# LEDs.net
KiCad netlist of a schematic drawn in EAGLE
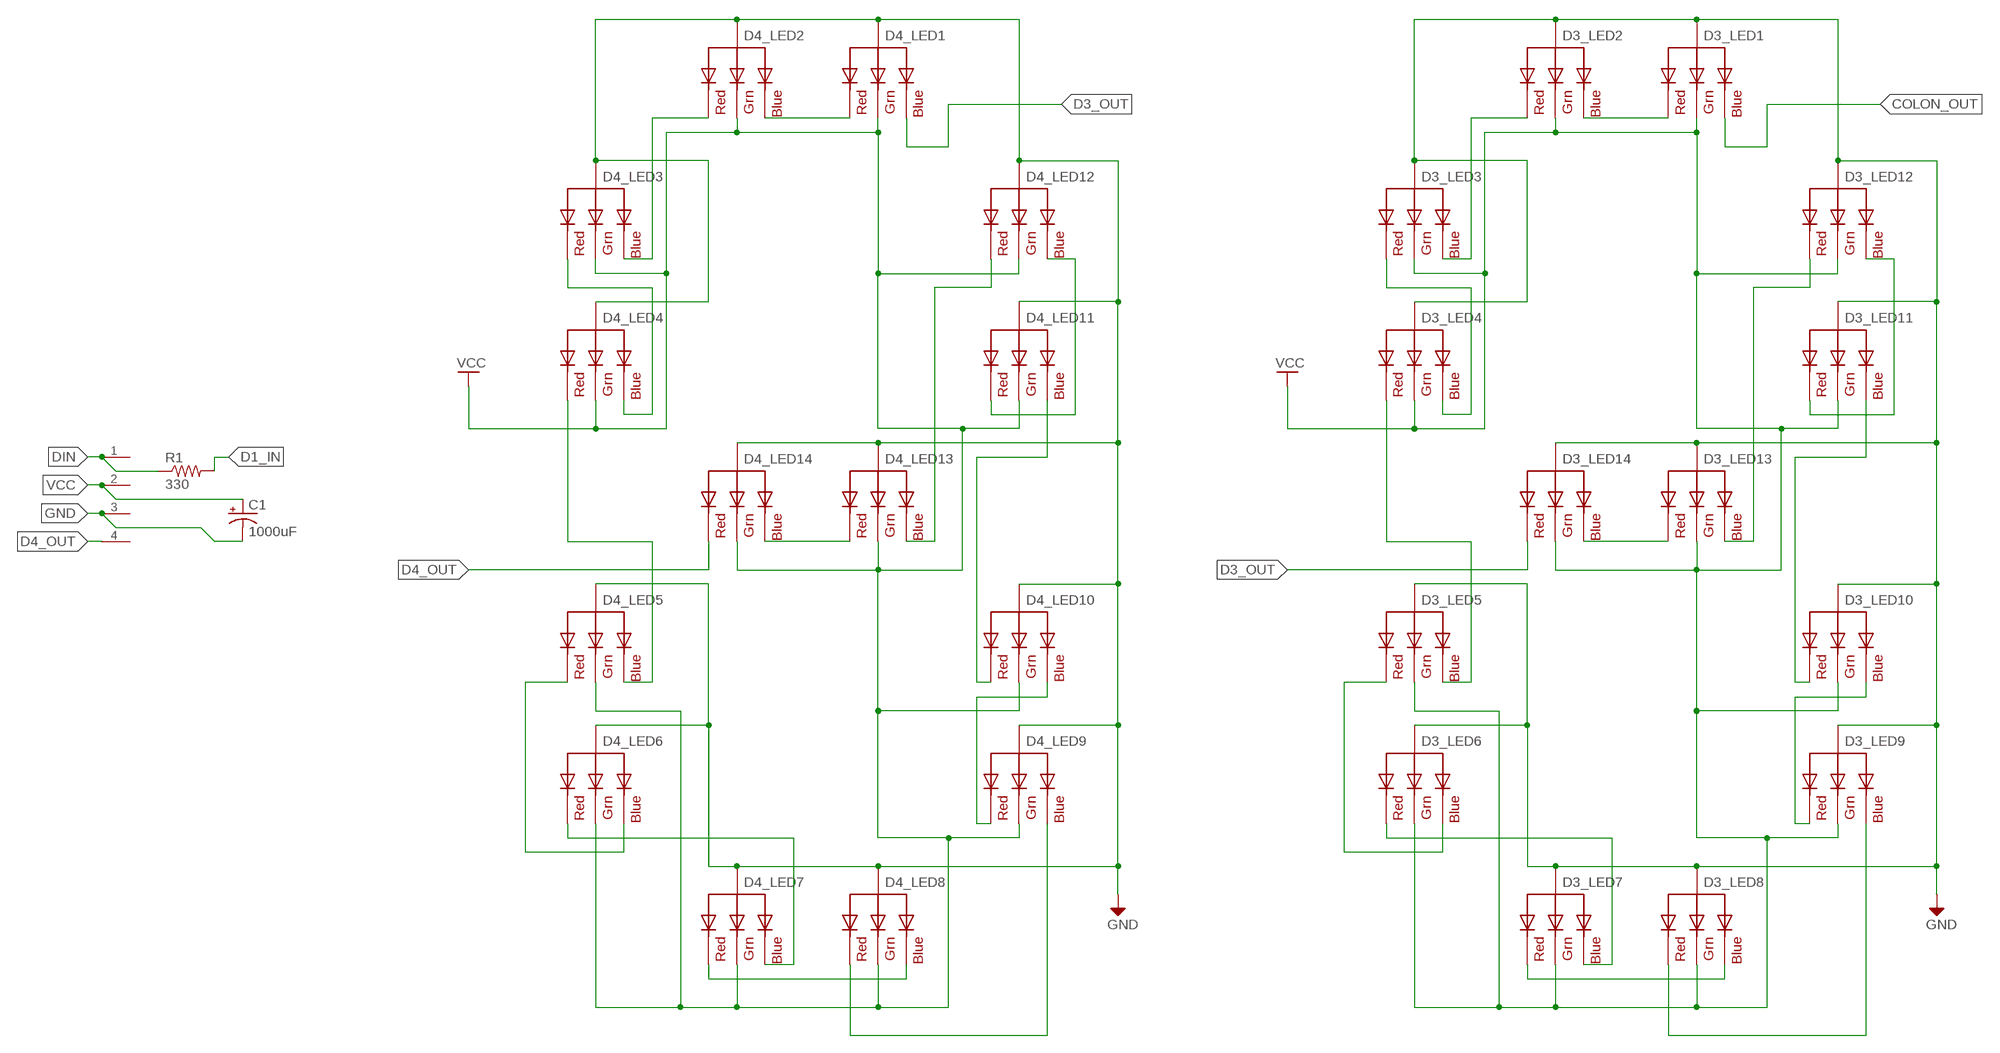
[diagram p0: schematic, sheet 1, part 1 of 2]
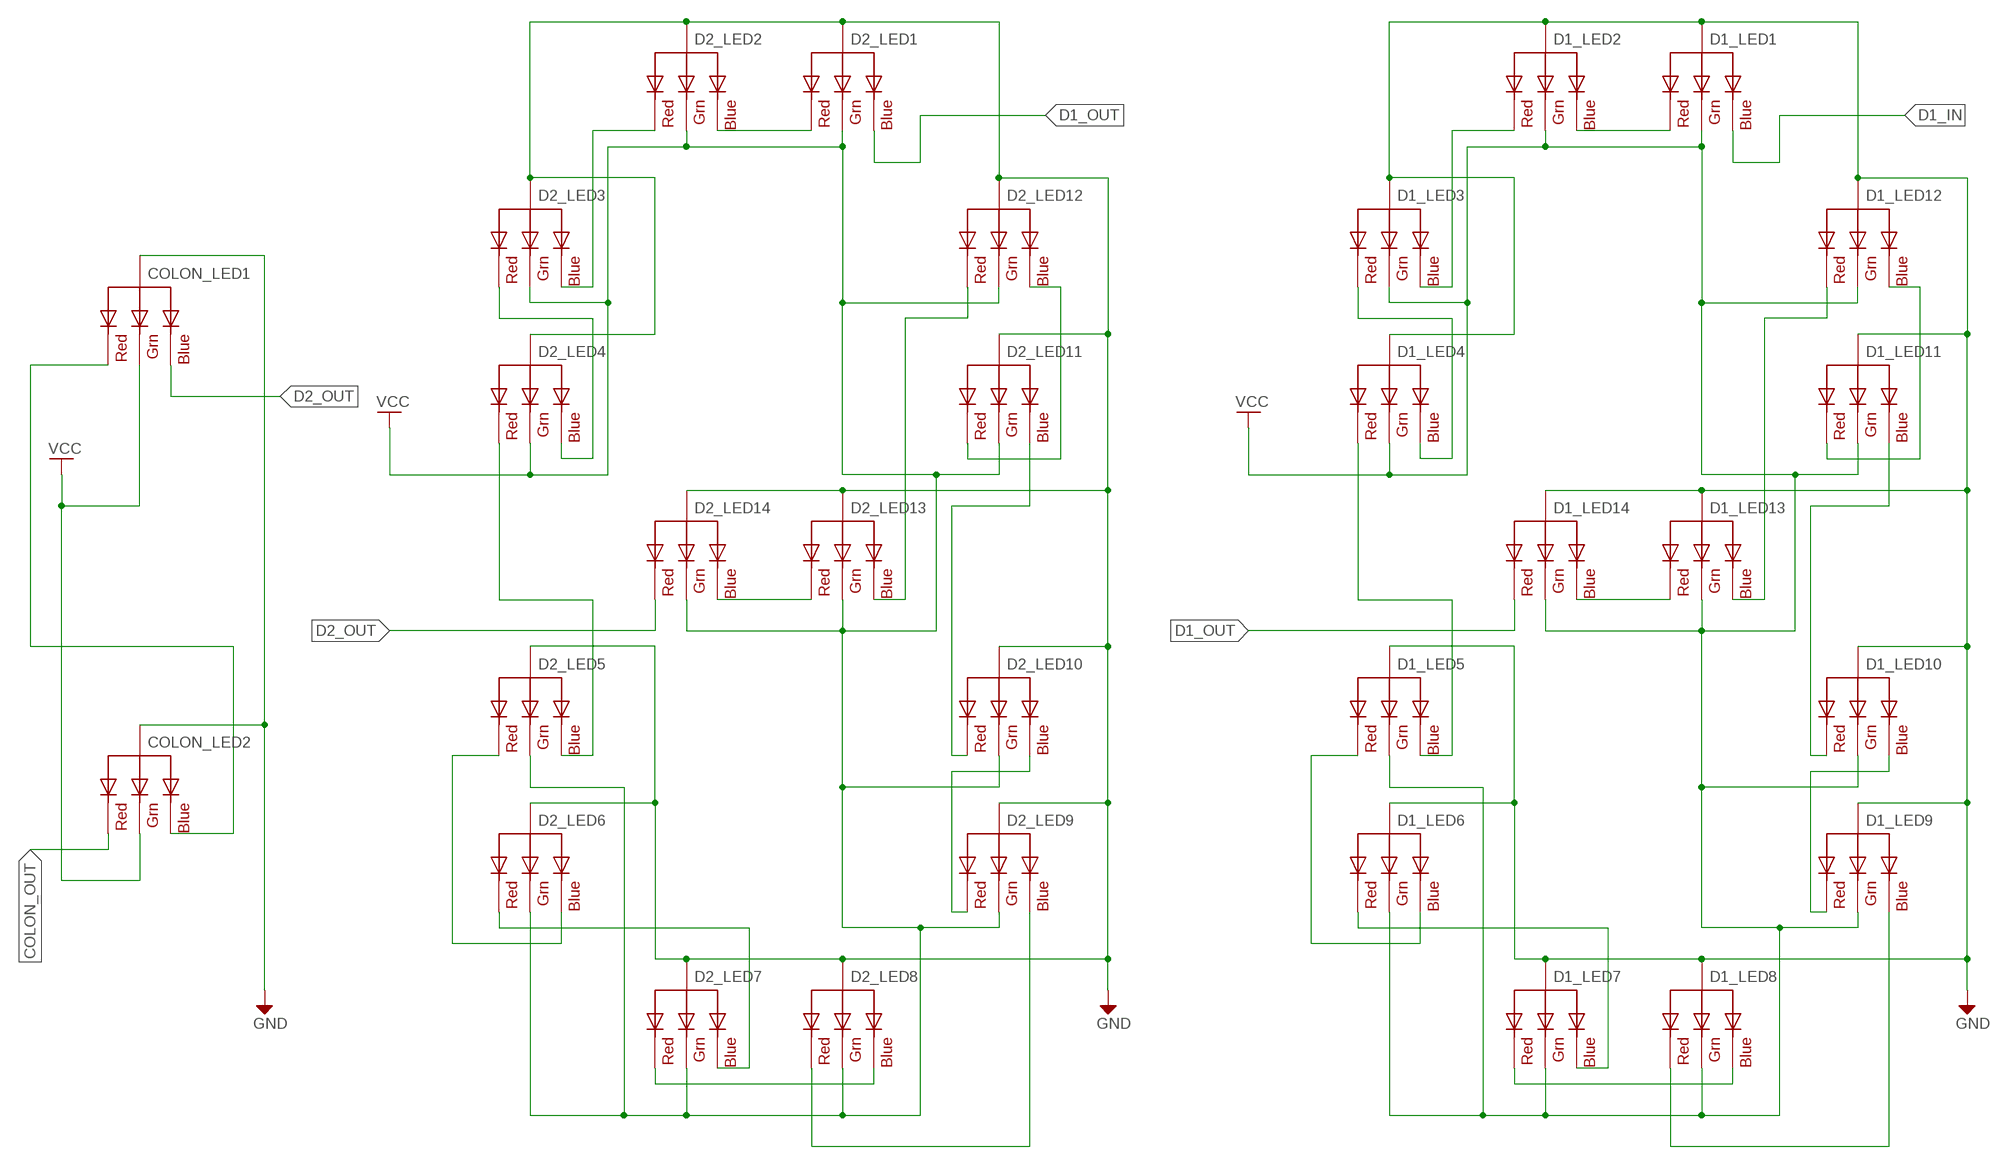
[diagram p1: schematic, sheet 1, part 2 of 2]

(export (version "E")
  (design (tool "Eeschema 10.0.6"))
  (components
    (comp (ref "C1")
      (value "1000uF")
      (footprint "eagle-import:E2,5-6")
      (libsource (lib "eagle-import") (part "CPOL-USE2.5-6"))
    )
    (comp (ref "COLON_LED1")
      (value "RGBLED_CA-5MM")
      (footprint "eagle-import:LED5MMRGB")
      (libsource (lib "eagle-import") (part "RGBLED_CA-5MM"))
    )
    (comp (ref "COLON_LED2")
      (value "RGBLED_CA-5MM")
      (footprint "eagle-import:LED5MMRGB")
      (libsource (lib "eagle-import") (part "RGBLED_CA-5MM"))
    )
    (comp (ref "D1_LED1")
      (value "RGBLED_CA-5MM")
      (footprint "eagle-import:LED5MMRGB")
      (libsource (lib "eagle-import") (part "RGBLED_CA-5MM"))
    )
    (comp (ref "D1_LED2")
      (value "RGBLED_CA-5MM")
      (footprint "eagle-import:LED5MMRGB")
      (libsource (lib "eagle-import") (part "RGBLED_CA-5MM"))
    )
    (comp (ref "D1_LED3")
      (value "RGBLED_CA-5MM")
      (footprint "eagle-import:LED5MMRGB")
      (libsource (lib "eagle-import") (part "RGBLED_CA-5MM"))
    )
    (comp (ref "D1_LED4")
      (value "RGBLED_CA-5MM")
      (footprint "eagle-import:LED5MMRGB")
      (libsource (lib "eagle-import") (part "RGBLED_CA-5MM"))
    )
    (comp (ref "D1_LED5")
      (value "RGBLED_CA-5MM")
      (footprint "eagle-import:LED5MMRGB")
      (libsource (lib "eagle-import") (part "RGBLED_CA-5MM"))
    )
    (comp (ref "D1_LED6")
      (value "RGBLED_CA-5MM")
      (footprint "eagle-import:LED5MMRGB")
      (libsource (lib "eagle-import") (part "RGBLED_CA-5MM"))
    )
    (comp (ref "D1_LED7")
      (value "RGBLED_CA-5MM")
      (footprint "eagle-import:LED5MMRGB")
      (libsource (lib "eagle-import") (part "RGBLED_CA-5MM"))
    )
    (comp (ref "D1_LED8")
      (value "RGBLED_CA-5MM")
      (footprint "eagle-import:LED5MMRGB")
      (libsource (lib "eagle-import") (part "RGBLED_CA-5MM"))
    )
    (comp (ref "D1_LED9")
      (value "RGBLED_CA-5MM")
      (footprint "eagle-import:LED5MMRGB")
      (libsource (lib "eagle-import") (part "RGBLED_CA-5MM"))
    )
    (comp (ref "D1_LED10")
      (value "RGBLED_CA-5MM")
      (footprint "eagle-import:LED5MMRGB")
      (libsource (lib "eagle-import") (part "RGBLED_CA-5MM"))
    )
    (comp (ref "D1_LED11")
      (value "RGBLED_CA-5MM")
      (footprint "eagle-import:LED5MMRGB")
      (libsource (lib "eagle-import") (part "RGBLED_CA-5MM"))
    )
    (comp (ref "D1_LED12")
      (value "RGBLED_CA-5MM")
      (footprint "eagle-import:LED5MMRGB")
      (libsource (lib "eagle-import") (part "RGBLED_CA-5MM"))
    )
    (comp (ref "D1_LED13")
      (value "RGBLED_CA-5MM")
      (footprint "eagle-import:LED5MMRGB")
      (libsource (lib "eagle-import") (part "RGBLED_CA-5MM"))
    )
    (comp (ref "D1_LED14")
      (value "RGBLED_CA-5MM")
      (footprint "eagle-import:LED5MMRGB")
      (libsource (lib "eagle-import") (part "RGBLED_CA-5MM"))
    )
    (comp (ref "D2_LED1")
      (value "RGBLED_CA-5MM")
      (footprint "eagle-import:LED5MMRGB")
      (libsource (lib "eagle-import") (part "RGBLED_CA-5MM"))
    )
    (comp (ref "D2_LED2")
      (value "RGBLED_CA-5MM")
      (footprint "eagle-import:LED5MMRGB")
      (libsource (lib "eagle-import") (part "RGBLED_CA-5MM"))
    )
    (comp (ref "D2_LED3")
      (value "RGBLED_CA-5MM")
      (footprint "eagle-import:LED5MMRGB")
      (libsource (lib "eagle-import") (part "RGBLED_CA-5MM"))
    )
    (comp (ref "D2_LED4")
      (value "RGBLED_CA-5MM")
      (footprint "eagle-import:LED5MMRGB")
      (libsource (lib "eagle-import") (part "RGBLED_CA-5MM"))
    )
    (comp (ref "D2_LED5")
      (value "RGBLED_CA-5MM")
      (footprint "eagle-import:LED5MMRGB")
      (libsource (lib "eagle-import") (part "RGBLED_CA-5MM"))
    )
    (comp (ref "D2_LED6")
      (value "RGBLED_CA-5MM")
      (footprint "eagle-import:LED5MMRGB")
      (libsource (lib "eagle-import") (part "RGBLED_CA-5MM"))
    )
    (comp (ref "D2_LED7")
      (value "RGBLED_CA-5MM")
      (footprint "eagle-import:LED5MMRGB")
      (libsource (lib "eagle-import") (part "RGBLED_CA-5MM"))
    )
    (comp (ref "D2_LED8")
      (value "RGBLED_CA-5MM")
      (footprint "eagle-import:LED5MMRGB")
      (libsource (lib "eagle-import") (part "RGBLED_CA-5MM"))
    )
    (comp (ref "D2_LED9")
      (value "RGBLED_CA-5MM")
      (footprint "eagle-import:LED5MMRGB")
      (libsource (lib "eagle-import") (part "RGBLED_CA-5MM"))
    )
    (comp (ref "D2_LED10")
      (value "RGBLED_CA-5MM")
      (footprint "eagle-import:LED5MMRGB")
      (libsource (lib "eagle-import") (part "RGBLED_CA-5MM"))
    )
    (comp (ref "D2_LED11")
      (value "RGBLED_CA-5MM")
      (footprint "eagle-import:LED5MMRGB")
      (libsource (lib "eagle-import") (part "RGBLED_CA-5MM"))
    )
    (comp (ref "D2_LED12")
      (value "RGBLED_CA-5MM")
      (footprint "eagle-import:LED5MMRGB")
      (libsource (lib "eagle-import") (part "RGBLED_CA-5MM"))
    )
    (comp (ref "D2_LED13")
      (value "RGBLED_CA-5MM")
      (footprint "eagle-import:LED5MMRGB")
      (libsource (lib "eagle-import") (part "RGBLED_CA-5MM"))
    )
    (comp (ref "D2_LED14")
      (value "RGBLED_CA-5MM")
      (footprint "eagle-import:LED5MMRGB")
      (libsource (lib "eagle-import") (part "RGBLED_CA-5MM"))
    )
    (comp (ref "D3_LED1")
      (value "RGBLED_CA-5MM")
      (footprint "eagle-import:LED5MMRGB")
      (libsource (lib "eagle-import") (part "RGBLED_CA-5MM"))
    )
    (comp (ref "D3_LED2")
      (value "RGBLED_CA-5MM")
      (footprint "eagle-import:LED5MMRGB")
      (libsource (lib "eagle-import") (part "RGBLED_CA-5MM"))
    )
    (comp (ref "D3_LED3")
      (value "RGBLED_CA-5MM")
      (footprint "eagle-import:LED5MMRGB")
      (libsource (lib "eagle-import") (part "RGBLED_CA-5MM"))
    )
    (comp (ref "D3_LED4")
      (value "RGBLED_CA-5MM")
      (footprint "eagle-import:LED5MMRGB")
      (libsource (lib "eagle-import") (part "RGBLED_CA-5MM"))
    )
    (comp (ref "D3_LED5")
      (value "RGBLED_CA-5MM")
      (footprint "eagle-import:LED5MMRGB")
      (libsource (lib "eagle-import") (part "RGBLED_CA-5MM"))
    )
    (comp (ref "D3_LED6")
      (value "RGBLED_CA-5MM")
      (footprint "eagle-import:LED5MMRGB")
      (libsource (lib "eagle-import") (part "RGBLED_CA-5MM"))
    )
    (comp (ref "D3_LED7")
      (value "RGBLED_CA-5MM")
      (footprint "eagle-import:LED5MMRGB")
      (libsource (lib "eagle-import") (part "RGBLED_CA-5MM"))
    )
    (comp (ref "D3_LED8")
      (value "RGBLED_CA-5MM")
      (footprint "eagle-import:LED5MMRGB")
      (libsource (lib "eagle-import") (part "RGBLED_CA-5MM"))
    )
    (comp (ref "D3_LED9")
      (value "RGBLED_CA-5MM")
      (footprint "eagle-import:LED5MMRGB")
      (libsource (lib "eagle-import") (part "RGBLED_CA-5MM"))
    )
    (comp (ref "D3_LED10")
      (value "RGBLED_CA-5MM")
      (footprint "eagle-import:LED5MMRGB")
      (libsource (lib "eagle-import") (part "RGBLED_CA-5MM"))
    )
    (comp (ref "D3_LED11")
      (value "RGBLED_CA-5MM")
      (footprint "eagle-import:LED5MMRGB")
      (libsource (lib "eagle-import") (part "RGBLED_CA-5MM"))
    )
    (comp (ref "D3_LED12")
      (value "RGBLED_CA-5MM")
      (footprint "eagle-import:LED5MMRGB")
      (libsource (lib "eagle-import") (part "RGBLED_CA-5MM"))
    )
    (comp (ref "D3_LED13")
      (value "RGBLED_CA-5MM")
      (footprint "eagle-import:LED5MMRGB")
      (libsource (lib "eagle-import") (part "RGBLED_CA-5MM"))
    )
    (comp (ref "D3_LED14")
      (value "RGBLED_CA-5MM")
      (footprint "eagle-import:LED5MMRGB")
      (libsource (lib "eagle-import") (part "RGBLED_CA-5MM"))
    )
    (comp (ref "D4_LED1")
      (value "RGBLED_CA-5MM")
      (footprint "eagle-import:LED5MMRGB")
      (libsource (lib "eagle-import") (part "RGBLED_CA-5MM"))
    )
    (comp (ref "D4_LED2")
      (value "RGBLED_CA-5MM")
      (footprint "eagle-import:LED5MMRGB")
      (libsource (lib "eagle-import") (part "RGBLED_CA-5MM"))
    )
    (comp (ref "D4_LED3")
      (value "RGBLED_CA-5MM")
      (footprint "eagle-import:LED5MMRGB")
      (libsource (lib "eagle-import") (part "RGBLED_CA-5MM"))
    )
    (comp (ref "D4_LED4")
      (value "RGBLED_CA-5MM")
      (footprint "eagle-import:LED5MMRGB")
      (libsource (lib "eagle-import") (part "RGBLED_CA-5MM"))
    )
    (comp (ref "D4_LED5")
      (value "RGBLED_CA-5MM")
      (footprint "eagle-import:LED5MMRGB")
      (libsource (lib "eagle-import") (part "RGBLED_CA-5MM"))
    )
    (comp (ref "D4_LED6")
      (value "RGBLED_CA-5MM")
      (footprint "eagle-import:LED5MMRGB")
      (libsource (lib "eagle-import") (part "RGBLED_CA-5MM"))
    )
    (comp (ref "D4_LED7")
      (value "RGBLED_CA-5MM")
      (footprint "eagle-import:LED5MMRGB")
      (libsource (lib "eagle-import") (part "RGBLED_CA-5MM"))
    )
    (comp (ref "D4_LED8")
      (value "RGBLED_CA-5MM")
      (footprint "eagle-import:LED5MMRGB")
      (libsource (lib "eagle-import") (part "RGBLED_CA-5MM"))
    )
    (comp (ref "D4_LED9")
      (value "RGBLED_CA-5MM")
      (footprint "eagle-import:LED5MMRGB")
      (libsource (lib "eagle-import") (part "RGBLED_CA-5MM"))
    )
    (comp (ref "D4_LED10")
      (value "RGBLED_CA-5MM")
      (footprint "eagle-import:LED5MMRGB")
      (libsource (lib "eagle-import") (part "RGBLED_CA-5MM"))
    )
    (comp (ref "D4_LED11")
      (value "RGBLED_CA-5MM")
      (footprint "eagle-import:LED5MMRGB")
      (libsource (lib "eagle-import") (part "RGBLED_CA-5MM"))
    )
    (comp (ref "D4_LED12")
      (value "RGBLED_CA-5MM")
      (footprint "eagle-import:LED5MMRGB")
      (libsource (lib "eagle-import") (part "RGBLED_CA-5MM"))
    )
    (comp (ref "D4_LED13")
      (value "RGBLED_CA-5MM")
      (footprint "eagle-import:LED5MMRGB")
      (libsource (lib "eagle-import") (part "RGBLED_CA-5MM"))
    )
    (comp (ref "D4_LED14")
      (value "RGBLED_CA-5MM")
      (footprint "eagle-import:LED5MMRGB")
      (libsource (lib "eagle-import") (part "RGBLED_CA-5MM"))
    )
    (comp (ref "R1")
      (value "330")
      (footprint "eagle-import:R0805")
      (libsource (lib "eagle-import") (part "R-US_R0805"))
    )
    (comp (ref "U$1")
      (value "HEADER-1X4")
      (footprint "eagle-import:HEADER-1X4")
      (libsource (lib "eagle-import") (part "HEADER-1X4"))
    )
  )
  (nets
    (net (code "1") (name "COLON_OUT") (class "Default")
      (node (ref "COLON_LED2") (pin "1") (pinfunction "RED_1") (pintype "bidirectional"))
      (node (ref "D3_LED1") (pin "4") (pinfunction "BLUE_4") (pintype "bidirectional"))
    )
    (net (code "2") (name "D1_IN") (class "Default")
      (node (ref "D1_LED1") (pin "4") (pinfunction "BLUE_4") (pintype "bidirectional"))
      (node (ref "R1") (pin "2") (pinfunction "2_2") (pintype "passive"))
    )
    (net (code "3") (name "D1_OUT") (class "Default")
      (node (ref "D1_LED14") (pin "1") (pinfunction "RED_1") (pintype "bidirectional"))
      (node (ref "D2_LED1") (pin "4") (pinfunction "BLUE_4") (pintype "bidirectional"))
    )
    (net (code "4") (name "D2_OUT") (class "Default")
      (node (ref "COLON_LED1") (pin "4") (pinfunction "BLUE_4") (pintype "bidirectional"))
      (node (ref "D2_LED14") (pin "1") (pinfunction "RED_1") (pintype "bidirectional"))
    )
    (net (code "5") (name "D3_OUT") (class "Default")
      (node (ref "D3_LED14") (pin "1") (pinfunction "RED_1") (pintype "bidirectional"))
      (node (ref "D4_LED1") (pin "4") (pinfunction "BLUE_4") (pintype "bidirectional"))
    )
    (net (code "6") (name "D4_OUT") (class "Default")
      (node (ref "D4_LED14") (pin "1") (pinfunction "RED_1") (pintype "bidirectional"))
      (node (ref "U$1") (pin "4") (pinfunction "4_4") (pintype "bidirectional"))
    )
    (net (code "7") (name "DIN") (class "Default")
      (node (ref "R1") (pin "1") (pinfunction "1_1") (pintype "passive"))
      (node (ref "U$1") (pin "1") (pinfunction "1_1") (pintype "bidirectional"))
    )
    (net (code "8") (name "GND") (class "Default")
      (node (ref "C1") (pin "-") (pinfunction "-_-") (pintype "passive"))
      (node (ref "COLON_LED1") (pin "2") (pinfunction "VCC_2") (pintype "bidirectional"))
      (node (ref "COLON_LED2") (pin "2") (pinfunction "VCC_2") (pintype "bidirectional"))
      (node (ref "D1_LED1") (pin "2") (pinfunction "VCC_2") (pintype "bidirectional"))
      (node (ref "D1_LED10") (pin "2") (pinfunction "VCC_2") (pintype "bidirectional"))
      (node (ref "D1_LED11") (pin "2") (pinfunction "VCC_2") (pintype "bidirectional"))
      (node (ref "D1_LED12") (pin "2") (pinfunction "VCC_2") (pintype "bidirectional"))
      (node (ref "D1_LED13") (pin "2") (pinfunction "VCC_2") (pintype "bidirectional"))
      (node (ref "D1_LED14") (pin "2") (pinfunction "VCC_2") (pintype "bidirectional"))
      (node (ref "D1_LED2") (pin "2") (pinfunction "VCC_2") (pintype "bidirectional"))
      (node (ref "D1_LED3") (pin "2") (pinfunction "VCC_2") (pintype "bidirectional"))
      (node (ref "D1_LED4") (pin "2") (pinfunction "VCC_2") (pintype "bidirectional"))
      (node (ref "D1_LED5") (pin "2") (pinfunction "VCC_2") (pintype "bidirectional"))
      (node (ref "D1_LED6") (pin "2") (pinfunction "VCC_2") (pintype "bidirectional"))
      (node (ref "D1_LED7") (pin "2") (pinfunction "VCC_2") (pintype "bidirectional"))
      (node (ref "D1_LED8") (pin "2") (pinfunction "VCC_2") (pintype "bidirectional"))
      (node (ref "D1_LED9") (pin "2") (pinfunction "VCC_2") (pintype "bidirectional"))
      (node (ref "D2_LED1") (pin "2") (pinfunction "VCC_2") (pintype "bidirectional"))
      (node (ref "D2_LED10") (pin "2") (pinfunction "VCC_2") (pintype "bidirectional"))
      (node (ref "D2_LED11") (pin "2") (pinfunction "VCC_2") (pintype "bidirectional"))
      (node (ref "D2_LED12") (pin "2") (pinfunction "VCC_2") (pintype "bidirectional"))
      (node (ref "D2_LED13") (pin "2") (pinfunction "VCC_2") (pintype "bidirectional"))
      (node (ref "D2_LED14") (pin "2") (pinfunction "VCC_2") (pintype "bidirectional"))
      (node (ref "D2_LED2") (pin "2") (pinfunction "VCC_2") (pintype "bidirectional"))
      (node (ref "D2_LED3") (pin "2") (pinfunction "VCC_2") (pintype "bidirectional"))
      (node (ref "D2_LED4") (pin "2") (pinfunction "VCC_2") (pintype "bidirectional"))
      (node (ref "D2_LED5") (pin "2") (pinfunction "VCC_2") (pintype "bidirectional"))
      (node (ref "D2_LED6") (pin "2") (pinfunction "VCC_2") (pintype "bidirectional"))
      (node (ref "D2_LED7") (pin "2") (pinfunction "VCC_2") (pintype "bidirectional"))
      (node (ref "D2_LED8") (pin "2") (pinfunction "VCC_2") (pintype "bidirectional"))
      (node (ref "D2_LED9") (pin "2") (pinfunction "VCC_2") (pintype "bidirectional"))
      (node (ref "D3_LED1") (pin "2") (pinfunction "VCC_2") (pintype "bidirectional"))
      (node (ref "D3_LED10") (pin "2") (pinfunction "VCC_2") (pintype "bidirectional"))
      (node (ref "D3_LED11") (pin "2") (pinfunction "VCC_2") (pintype "bidirectional"))
      (node (ref "D3_LED12") (pin "2") (pinfunction "VCC_2") (pintype "bidirectional"))
      (node (ref "D3_LED13") (pin "2") (pinfunction "VCC_2") (pintype "bidirectional"))
      (node (ref "D3_LED14") (pin "2") (pinfunction "VCC_2") (pintype "bidirectional"))
      (node (ref "D3_LED2") (pin "2") (pinfunction "VCC_2") (pintype "bidirectional"))
      (node (ref "D3_LED3") (pin "2") (pinfunction "VCC_2") (pintype "bidirectional"))
      (node (ref "D3_LED4") (pin "2") (pinfunction "VCC_2") (pintype "bidirectional"))
      (node (ref "D3_LED5") (pin "2") (pinfunction "VCC_2") (pintype "bidirectional"))
      (node (ref "D3_LED6") (pin "2") (pinfunction "VCC_2") (pintype "bidirectional"))
      (node (ref "D3_LED7") (pin "2") (pinfunction "VCC_2") (pintype "bidirectional"))
      (node (ref "D3_LED8") (pin "2") (pinfunction "VCC_2") (pintype "bidirectional"))
      (node (ref "D3_LED9") (pin "2") (pinfunction "VCC_2") (pintype "bidirectional"))
      (node (ref "D4_LED1") (pin "2") (pinfunction "VCC_2") (pintype "bidirectional"))
      (node (ref "D4_LED10") (pin "2") (pinfunction "VCC_2") (pintype "bidirectional"))
      (node (ref "D4_LED11") (pin "2") (pinfunction "VCC_2") (pintype "bidirectional"))
      (node (ref "D4_LED12") (pin "2") (pinfunction "VCC_2") (pintype "bidirectional"))
      (node (ref "D4_LED13") (pin "2") (pinfunction "VCC_2") (pintype "bidirectional"))
      (node (ref "D4_LED14") (pin "2") (pinfunction "VCC_2") (pintype "bidirectional"))
      (node (ref "D4_LED2") (pin "2") (pinfunction "VCC_2") (pintype "bidirectional"))
      (node (ref "D4_LED3") (pin "2") (pinfunction "VCC_2") (pintype "bidirectional"))
      (node (ref "D4_LED4") (pin "2") (pinfunction "VCC_2") (pintype "bidirectional"))
      (node (ref "D4_LED5") (pin "2") (pinfunction "VCC_2") (pintype "bidirectional"))
      (node (ref "D4_LED6") (pin "2") (pinfunction "VCC_2") (pintype "bidirectional"))
      (node (ref "D4_LED7") (pin "2") (pinfunction "VCC_2") (pintype "bidirectional"))
      (node (ref "D4_LED8") (pin "2") (pinfunction "VCC_2") (pintype "bidirectional"))
      (node (ref "D4_LED9") (pin "2") (pinfunction "VCC_2") (pintype "bidirectional"))
      (node (ref "U$1") (pin "3") (pinfunction "3_3") (pintype "bidirectional"))
    )
    (net (code "9") (name "Net-(COLON_LED1-RED)") (class "Default")
      (node (ref "COLON_LED1") (pin "1") (pinfunction "RED_1") (pintype "bidirectional"))
      (node (ref "COLON_LED2") (pin "4") (pinfunction "BLUE_4") (pintype "bidirectional"))
    )
    (net (code "10") (name "Net-(D1_LED1-RED)") (class "Default")
      (node (ref "D1_LED1") (pin "1") (pinfunction "RED_1") (pintype "bidirectional"))
      (node (ref "D1_LED2") (pin "4") (pinfunction "BLUE_4") (pintype "bidirectional"))
    )
    (net (code "11") (name "Net-(D1_LED2-RED)") (class "Default")
      (node (ref "D1_LED2") (pin "1") (pinfunction "RED_1") (pintype "bidirectional"))
      (node (ref "D1_LED3") (pin "4") (pinfunction "BLUE_4") (pintype "bidirectional"))
    )
    (net (code "12") (name "Net-(D1_LED3-RED)") (class "Default")
      (node (ref "D1_LED3") (pin "1") (pinfunction "RED_1") (pintype "bidirectional"))
      (node (ref "D1_LED4") (pin "4") (pinfunction "BLUE_4") (pintype "bidirectional"))
    )
    (net (code "13") (name "Net-(D1_LED4-RED)") (class "Default")
      (node (ref "D1_LED4") (pin "1") (pinfunction "RED_1") (pintype "bidirectional"))
      (node (ref "D1_LED5") (pin "4") (pinfunction "BLUE_4") (pintype "bidirectional"))
    )
    (net (code "14") (name "Net-(D1_LED5-RED)") (class "Default")
      (node (ref "D1_LED5") (pin "1") (pinfunction "RED_1") (pintype "bidirectional"))
      (node (ref "D1_LED6") (pin "4") (pinfunction "BLUE_4") (pintype "bidirectional"))
    )
    (net (code "15") (name "Net-(D1_LED6-RED)") (class "Default")
      (node (ref "D1_LED6") (pin "1") (pinfunction "RED_1") (pintype "bidirectional"))
      (node (ref "D1_LED7") (pin "4") (pinfunction "BLUE_4") (pintype "bidirectional"))
    )
    (net (code "16") (name "Net-(D1_LED7-RED)") (class "Default")
      (node (ref "D1_LED7") (pin "1") (pinfunction "RED_1") (pintype "bidirectional"))
      (node (ref "D1_LED8") (pin "4") (pinfunction "BLUE_4") (pintype "bidirectional"))
    )
    (net (code "17") (name "Net-(D1_LED8-RED)") (class "Default")
      (node (ref "D1_LED8") (pin "1") (pinfunction "RED_1") (pintype "bidirectional"))
      (node (ref "D1_LED9") (pin "4") (pinfunction "BLUE_4") (pintype "bidirectional"))
    )
    (net (code "18") (name "Net-(D1_LED10-BLUE)") (class "Default")
      (node (ref "D1_LED10") (pin "4") (pinfunction "BLUE_4") (pintype "bidirectional"))
      (node (ref "D1_LED9") (pin "1") (pinfunction "RED_1") (pintype "bidirectional"))
    )
    (net (code "19") (name "Net-(D1_LED10-RED)") (class "Default")
      (node (ref "D1_LED10") (pin "1") (pinfunction "RED_1") (pintype "bidirectional"))
      (node (ref "D1_LED11") (pin "4") (pinfunction "BLUE_4") (pintype "bidirectional"))
    )
    (net (code "20") (name "Net-(D1_LED11-RED)") (class "Default")
      (node (ref "D1_LED11") (pin "1") (pinfunction "RED_1") (pintype "bidirectional"))
      (node (ref "D1_LED12") (pin "4") (pinfunction "BLUE_4") (pintype "bidirectional"))
    )
    (net (code "21") (name "Net-(D1_LED12-RED)") (class "Default")
      (node (ref "D1_LED12") (pin "1") (pinfunction "RED_1") (pintype "bidirectional"))
      (node (ref "D1_LED13") (pin "4") (pinfunction "BLUE_4") (pintype "bidirectional"))
    )
    (net (code "22") (name "Net-(D1_LED13-RED)") (class "Default")
      (node (ref "D1_LED13") (pin "1") (pinfunction "RED_1") (pintype "bidirectional"))
      (node (ref "D1_LED14") (pin "4") (pinfunction "BLUE_4") (pintype "bidirectional"))
    )
    (net (code "23") (name "Net-(D2_LED1-RED)") (class "Default")
      (node (ref "D2_LED1") (pin "1") (pinfunction "RED_1") (pintype "bidirectional"))
      (node (ref "D2_LED2") (pin "4") (pinfunction "BLUE_4") (pintype "bidirectional"))
    )
    (net (code "24") (name "Net-(D2_LED2-RED)") (class "Default")
      (node (ref "D2_LED2") (pin "1") (pinfunction "RED_1") (pintype "bidirectional"))
      (node (ref "D2_LED3") (pin "4") (pinfunction "BLUE_4") (pintype "bidirectional"))
    )
    (net (code "25") (name "Net-(D2_LED3-RED)") (class "Default")
      (node (ref "D2_LED3") (pin "1") (pinfunction "RED_1") (pintype "bidirectional"))
      (node (ref "D2_LED4") (pin "4") (pinfunction "BLUE_4") (pintype "bidirectional"))
    )
    (net (code "26") (name "Net-(D2_LED4-RED)") (class "Default")
      (node (ref "D2_LED4") (pin "1") (pinfunction "RED_1") (pintype "bidirectional"))
      (node (ref "D2_LED5") (pin "4") (pinfunction "BLUE_4") (pintype "bidirectional"))
    )
    (net (code "27") (name "Net-(D2_LED5-RED)") (class "Default")
      (node (ref "D2_LED5") (pin "1") (pinfunction "RED_1") (pintype "bidirectional"))
      (node (ref "D2_LED6") (pin "4") (pinfunction "BLUE_4") (pintype "bidirectional"))
    )
    (net (code "28") (name "Net-(D2_LED6-RED)") (class "Default")
      (node (ref "D2_LED6") (pin "1") (pinfunction "RED_1") (pintype "bidirectional"))
      (node (ref "D2_LED7") (pin "4") (pinfunction "BLUE_4") (pintype "bidirectional"))
    )
    (net (code "29") (name "Net-(D2_LED7-RED)") (class "Default")
      (node (ref "D2_LED7") (pin "1") (pinfunction "RED_1") (pintype "bidirectional"))
      (node (ref "D2_LED8") (pin "4") (pinfunction "BLUE_4") (pintype "bidirectional"))
    )
    (net (code "30") (name "Net-(D2_LED8-RED)") (class "Default")
      (node (ref "D2_LED8") (pin "1") (pinfunction "RED_1") (pintype "bidirectional"))
      (node (ref "D2_LED9") (pin "4") (pinfunction "BLUE_4") (pintype "bidirectional"))
    )
    (net (code "31") (name "Net-(D2_LED10-BLUE)") (class "Default")
      (node (ref "D2_LED10") (pin "4") (pinfunction "BLUE_4") (pintype "bidirectional"))
      (node (ref "D2_LED9") (pin "1") (pinfunction "RED_1") (pintype "bidirectional"))
    )
    (net (code "32") (name "Net-(D2_LED10-RED)") (class "Default")
      (node (ref "D2_LED10") (pin "1") (pinfunction "RED_1") (pintype "bidirectional"))
      (node (ref "D2_LED11") (pin "4") (pinfunction "BLUE_4") (pintype "bidirectional"))
    )
    (net (code "33") (name "Net-(D2_LED11-RED)") (class "Default")
      (node (ref "D2_LED11") (pin "1") (pinfunction "RED_1") (pintype "bidirectional"))
      (node (ref "D2_LED12") (pin "4") (pinfunction "BLUE_4") (pintype "bidirectional"))
    )
    (net (code "34") (name "Net-(D2_LED12-RED)") (class "Default")
      (node (ref "D2_LED12") (pin "1") (pinfunction "RED_1") (pintype "bidirectional"))
      (node (ref "D2_LED13") (pin "4") (pinfunction "BLUE_4") (pintype "bidirectional"))
    )
    (net (code "35") (name "Net-(D2_LED13-RED)") (class "Default")
      (node (ref "D2_LED13") (pin "1") (pinfunction "RED_1") (pintype "bidirectional"))
      (node (ref "D2_LED14") (pin "4") (pinfunction "BLUE_4") (pintype "bidirectional"))
    )
    (net (code "36") (name "Net-(D3_LED1-RED)") (class "Default")
      (node (ref "D3_LED1") (pin "1") (pinfunction "RED_1") (pintype "bidirectional"))
      (node (ref "D3_LED2") (pin "4") (pinfunction "BLUE_4") (pintype "bidirectional"))
    )
    (net (code "37") (name "Net-(D3_LED2-RED)") (class "Default")
      (node (ref "D3_LED2") (pin "1") (pinfunction "RED_1") (pintype "bidirectional"))
      (node (ref "D3_LED3") (pin "4") (pinfunction "BLUE_4") (pintype "bidirectional"))
    )
    (net (code "38") (name "Net-(D3_LED3-RED)") (class "Default")
      (node (ref "D3_LED3") (pin "1") (pinfunction "RED_1") (pintype "bidirectional"))
      (node (ref "D3_LED4") (pin "4") (pinfunction "BLUE_4") (pintype "bidirectional"))
    )
    (net (code "39") (name "Net-(D3_LED4-RED)") (class "Default")
      (node (ref "D3_LED4") (pin "1") (pinfunction "RED_1") (pintype "bidirectional"))
      (node (ref "D3_LED5") (pin "4") (pinfunction "BLUE_4") (pintype "bidirectional"))
    )
    (net (code "40") (name "Net-(D3_LED5-RED)") (class "Default")
      (node (ref "D3_LED5") (pin "1") (pinfunction "RED_1") (pintype "bidirectional"))
      (node (ref "D3_LED6") (pin "4") (pinfunction "BLUE_4") (pintype "bidirectional"))
    )
    (net (code "41") (name "Net-(D3_LED6-RED)") (class "Default")
      (node (ref "D3_LED6") (pin "1") (pinfunction "RED_1") (pintype "bidirectional"))
      (node (ref "D3_LED7") (pin "4") (pinfunction "BLUE_4") (pintype "bidirectional"))
    )
    (net (code "42") (name "Net-(D3_LED7-RED)") (class "Default")
      (node (ref "D3_LED7") (pin "1") (pinfunction "RED_1") (pintype "bidirectional"))
      (node (ref "D3_LED8") (pin "4") (pinfunction "BLUE_4") (pintype "bidirectional"))
    )
    (net (code "43") (name "Net-(D3_LED8-RED)") (class "Default")
      (node (ref "D3_LED8") (pin "1") (pinfunction "RED_1") (pintype "bidirectional"))
      (node (ref "D3_LED9") (pin "4") (pinfunction "BLUE_4") (pintype "bidirectional"))
    )
    (net (code "44") (name "Net-(D3_LED10-BLUE)") (class "Default")
      (node (ref "D3_LED10") (pin "4") (pinfunction "BLUE_4") (pintype "bidirectional"))
      (node (ref "D3_LED9") (pin "1") (pinfunction "RED_1") (pintype "bidirectional"))
    )
    (net (code "45") (name "Net-(D3_LED10-RED)") (class "Default")
      (node (ref "D3_LED10") (pin "1") (pinfunction "RED_1") (pintype "bidirectional"))
      (node (ref "D3_LED11") (pin "4") (pinfunction "BLUE_4") (pintype "bidirectional"))
    )
    (net (code "46") (name "Net-(D3_LED11-RED)") (class "Default")
      (node (ref "D3_LED11") (pin "1") (pinfunction "RED_1") (pintype "bidirectional"))
      (node (ref "D3_LED12") (pin "4") (pinfunction "BLUE_4") (pintype "bidirectional"))
    )
    (net (code "47") (name "Net-(D3_LED12-RED)") (class "Default")
      (node (ref "D3_LED12") (pin "1") (pinfunction "RED_1") (pintype "bidirectional"))
      (node (ref "D3_LED13") (pin "4") (pinfunction "BLUE_4") (pintype "bidirectional"))
    )
    (net (code "48") (name "Net-(D3_LED13-RED)") (class "Default")
      (node (ref "D3_LED13") (pin "1") (pinfunction "RED_1") (pintype "bidirectional"))
      (node (ref "D3_LED14") (pin "4") (pinfunction "BLUE_4") (pintype "bidirectional"))
    )
    (net (code "49") (name "Net-(D4_LED1-RED)") (class "Default")
      (node (ref "D4_LED1") (pin "1") (pinfunction "RED_1") (pintype "bidirectional"))
      (node (ref "D4_LED2") (pin "4") (pinfunction "BLUE_4") (pintype "bidirectional"))
    )
    (net (code "50") (name "Net-(D4_LED2-RED)") (class "Default")
      (node (ref "D4_LED2") (pin "1") (pinfunction "RED_1") (pintype "bidirectional"))
      (node (ref "D4_LED3") (pin "4") (pinfunction "BLUE_4") (pintype "bidirectional"))
    )
    (net (code "51") (name "Net-(D4_LED3-RED)") (class "Default")
      (node (ref "D4_LED3") (pin "1") (pinfunction "RED_1") (pintype "bidirectional"))
      (node (ref "D4_LED4") (pin "4") (pinfunction "BLUE_4") (pintype "bidirectional"))
    )
    (net (code "52") (name "Net-(D4_LED4-RED)") (class "Default")
      (node (ref "D4_LED4") (pin "1") (pinfunction "RED_1") (pintype "bidirectional"))
      (node (ref "D4_LED5") (pin "4") (pinfunction "BLUE_4") (pintype "bidirectional"))
    )
    (net (code "53") (name "Net-(D4_LED5-RED)") (class "Default")
      (node (ref "D4_LED5") (pin "1") (pinfunction "RED_1") (pintype "bidirectional"))
      (node (ref "D4_LED6") (pin "4") (pinfunction "BLUE_4") (pintype "bidirectional"))
    )
    (net (code "54") (name "Net-(D4_LED6-RED)") (class "Default")
      (node (ref "D4_LED6") (pin "1") (pinfunction "RED_1") (pintype "bidirectional"))
      (node (ref "D4_LED7") (pin "4") (pinfunction "BLUE_4") (pintype "bidirectional"))
    )
    (net (code "55") (name "Net-(D4_LED7-RED)") (class "Default")
      (node (ref "D4_LED7") (pin "1") (pinfunction "RED_1") (pintype "bidirectional"))
      (node (ref "D4_LED8") (pin "4") (pinfunction "BLUE_4") (pintype "bidirectional"))
    )
    (net (code "56") (name "Net-(D4_LED8-RED)") (class "Default")
      (node (ref "D4_LED8") (pin "1") (pinfunction "RED_1") (pintype "bidirectional"))
      (node (ref "D4_LED9") (pin "4") (pinfunction "BLUE_4") (pintype "bidirectional"))
    )
    (net (code "57") (name "Net-(D4_LED10-BLUE)") (class "Default")
      (node (ref "D4_LED10") (pin "4") (pinfunction "BLUE_4") (pintype "bidirectional"))
      (node (ref "D4_LED9") (pin "1") (pinfunction "RED_1") (pintype "bidirectional"))
    )
    (net (code "58") (name "Net-(D4_LED10-RED)") (class "Default")
      (node (ref "D4_LED10") (pin "1") (pinfunction "RED_1") (pintype "bidirectional"))
      (node (ref "D4_LED11") (pin "4") (pinfunction "BLUE_4") (pintype "bidirectional"))
    )
    (net (code "59") (name "Net-(D4_LED11-RED)") (class "Default")
      (node (ref "D4_LED11") (pin "1") (pinfunction "RED_1") (pintype "bidirectional"))
      (node (ref "D4_LED12") (pin "4") (pinfunction "BLUE_4") (pintype "bidirectional"))
    )
    (net (code "60") (name "Net-(D4_LED12-RED)") (class "Default")
      (node (ref "D4_LED12") (pin "1") (pinfunction "RED_1") (pintype "bidirectional"))
      (node (ref "D4_LED13") (pin "4") (pinfunction "BLUE_4") (pintype "bidirectional"))
    )
    (net (code "61") (name "Net-(D4_LED13-RED)") (class "Default")
      (node (ref "D4_LED13") (pin "1") (pinfunction "RED_1") (pintype "bidirectional"))
      (node (ref "D4_LED14") (pin "4") (pinfunction "BLUE_4") (pintype "bidirectional"))
    )
    (net (code "62") (name "VCC") (class "Default")
      (node (ref "C1") (pin "+") (pinfunction "+_+") (pintype "passive"))
      (node (ref "COLON_LED1") (pin "3") (pinfunction "GREEN_3") (pintype "bidirectional"))
      (node (ref "COLON_LED2") (pin "3") (pinfunction "GREEN_3") (pintype "bidirectional"))
      (node (ref "D1_LED1") (pin "3") (pinfunction "GREEN_3") (pintype "bidirectional"))
      (node (ref "D1_LED10") (pin "3") (pinfunction "GREEN_3") (pintype "bidirectional"))
      (node (ref "D1_LED11") (pin "3") (pinfunction "GREEN_3") (pintype "bidirectional"))
      (node (ref "D1_LED12") (pin "3") (pinfunction "GREEN_3") (pintype "bidirectional"))
      (node (ref "D1_LED13") (pin "3") (pinfunction "GREEN_3") (pintype "bidirectional"))
      (node (ref "D1_LED14") (pin "3") (pinfunction "GREEN_3") (pintype "bidirectional"))
      (node (ref "D1_LED2") (pin "3") (pinfunction "GREEN_3") (pintype "bidirectional"))
      (node (ref "D1_LED3") (pin "3") (pinfunction "GREEN_3") (pintype "bidirectional"))
      (node (ref "D1_LED4") (pin "3") (pinfunction "GREEN_3") (pintype "bidirectional"))
      (node (ref "D1_LED5") (pin "3") (pinfunction "GREEN_3") (pintype "bidirectional"))
      (node (ref "D1_LED6") (pin "3") (pinfunction "GREEN_3") (pintype "bidirectional"))
      (node (ref "D1_LED7") (pin "3") (pinfunction "GREEN_3") (pintype "bidirectional"))
      (node (ref "D1_LED8") (pin "3") (pinfunction "GREEN_3") (pintype "bidirectional"))
      (node (ref "D1_LED9") (pin "3") (pinfunction "GREEN_3") (pintype "bidirectional"))
      (node (ref "D2_LED1") (pin "3") (pinfunction "GREEN_3") (pintype "bidirectional"))
      (node (ref "D2_LED10") (pin "3") (pinfunction "GREEN_3") (pintype "bidirectional"))
      (node (ref "D2_LED11") (pin "3") (pinfunction "GREEN_3") (pintype "bidirectional"))
      (node (ref "D2_LED12") (pin "3") (pinfunction "GREEN_3") (pintype "bidirectional"))
      (node (ref "D2_LED13") (pin "3") (pinfunction "GREEN_3") (pintype "bidirectional"))
      (node (ref "D2_LED14") (pin "3") (pinfunction "GREEN_3") (pintype "bidirectional"))
      (node (ref "D2_LED2") (pin "3") (pinfunction "GREEN_3") (pintype "bidirectional"))
      (node (ref "D2_LED3") (pin "3") (pinfunction "GREEN_3") (pintype "bidirectional"))
      (node (ref "D2_LED4") (pin "3") (pinfunction "GREEN_3") (pintype "bidirectional"))
      (node (ref "D2_LED5") (pin "3") (pinfunction "GREEN_3") (pintype "bidirectional"))
      (node (ref "D2_LED6") (pin "3") (pinfunction "GREEN_3") (pintype "bidirectional"))
      (node (ref "D2_LED7") (pin "3") (pinfunction "GREEN_3") (pintype "bidirectional"))
      (node (ref "D2_LED8") (pin "3") (pinfunction "GREEN_3") (pintype "bidirectional"))
      (node (ref "D2_LED9") (pin "3") (pinfunction "GREEN_3") (pintype "bidirectional"))
      (node (ref "D3_LED1") (pin "3") (pinfunction "GREEN_3") (pintype "bidirectional"))
      (node (ref "D3_LED10") (pin "3") (pinfunction "GREEN_3") (pintype "bidirectional"))
      (node (ref "D3_LED11") (pin "3") (pinfunction "GREEN_3") (pintype "bidirectional"))
      (node (ref "D3_LED12") (pin "3") (pinfunction "GREEN_3") (pintype "bidirectional"))
      (node (ref "D3_LED13") (pin "3") (pinfunction "GREEN_3") (pintype "bidirectional"))
      (node (ref "D3_LED14") (pin "3") (pinfunction "GREEN_3") (pintype "bidirectional"))
      (node (ref "D3_LED2") (pin "3") (pinfunction "GREEN_3") (pintype "bidirectional"))
      (node (ref "D3_LED3") (pin "3") (pinfunction "GREEN_3") (pintype "bidirectional"))
      (node (ref "D3_LED4") (pin "3") (pinfunction "GREEN_3") (pintype "bidirectional"))
      (node (ref "D3_LED5") (pin "3") (pinfunction "GREEN_3") (pintype "bidirectional"))
      (node (ref "D3_LED6") (pin "3") (pinfunction "GREEN_3") (pintype "bidirectional"))
      (node (ref "D3_LED7") (pin "3") (pinfunction "GREEN_3") (pintype "bidirectional"))
      (node (ref "D3_LED8") (pin "3") (pinfunction "GREEN_3") (pintype "bidirectional"))
      (node (ref "D3_LED9") (pin "3") (pinfunction "GREEN_3") (pintype "bidirectional"))
      (node (ref "D4_LED1") (pin "3") (pinfunction "GREEN_3") (pintype "bidirectional"))
      (node (ref "D4_LED10") (pin "3") (pinfunction "GREEN_3") (pintype "bidirectional"))
      (node (ref "D4_LED11") (pin "3") (pinfunction "GREEN_3") (pintype "bidirectional"))
      (node (ref "D4_LED12") (pin "3") (pinfunction "GREEN_3") (pintype "bidirectional"))
      (node (ref "D4_LED13") (pin "3") (pinfunction "GREEN_3") (pintype "bidirectional"))
      (node (ref "D4_LED14") (pin "3") (pinfunction "GREEN_3") (pintype "bidirectional"))
      (node (ref "D4_LED2") (pin "3") (pinfunction "GREEN_3") (pintype "bidirectional"))
      (node (ref "D4_LED3") (pin "3") (pinfunction "GREEN_3") (pintype "bidirectional"))
      (node (ref "D4_LED4") (pin "3") (pinfunction "GREEN_3") (pintype "bidirectional"))
      (node (ref "D4_LED5") (pin "3") (pinfunction "GREEN_3") (pintype "bidirectional"))
      (node (ref "D4_LED6") (pin "3") (pinfunction "GREEN_3") (pintype "bidirectional"))
      (node (ref "D4_LED7") (pin "3") (pinfunction "GREEN_3") (pintype "bidirectional"))
      (node (ref "D4_LED8") (pin "3") (pinfunction "GREEN_3") (pintype "bidirectional"))
      (node (ref "D4_LED9") (pin "3") (pinfunction "GREEN_3") (pintype "bidirectional"))
      (node (ref "U$1") (pin "2") (pinfunction "2_2") (pintype "bidirectional"))
    )
  )
)
